# ThrowBot_RX_Main_Board.net
KiCad netlist of a schematic drawn in Altium Designer
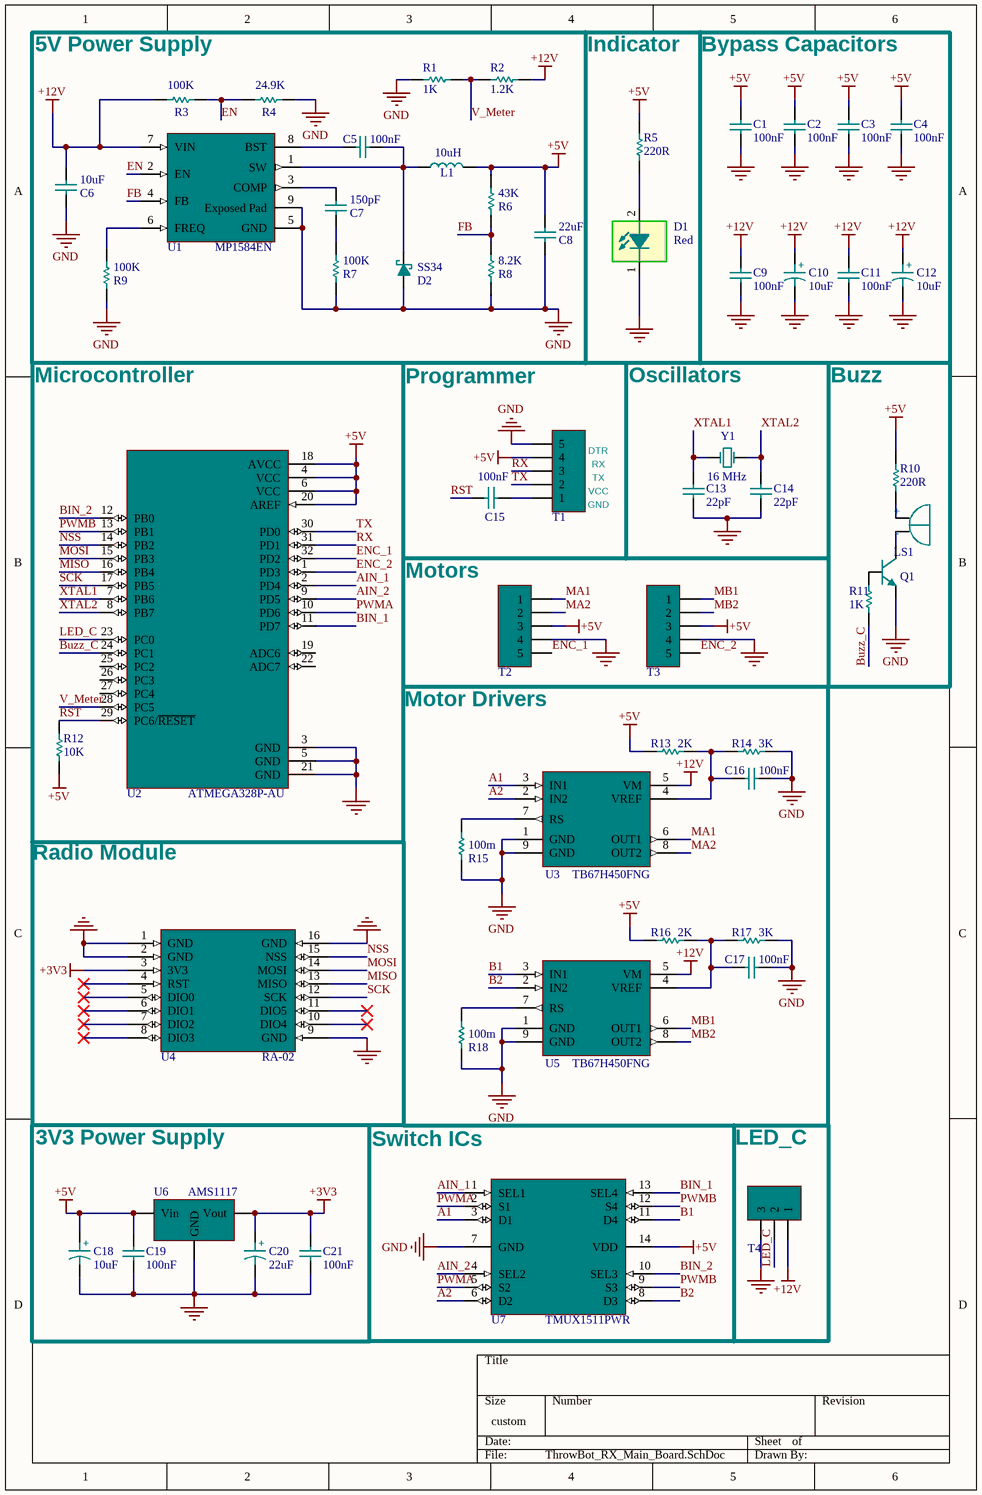
[diagram p0: ThrowBot_RX_Main_Board.SchDoc]

(export (version "E")
  (design (tool "Eeschema 10.0.6"))
  (components
    (comp (ref "C1")
      (value "Cap")
      (footprint "CAP 1206")
      (description "AVCC Cap")
      (fields (field (name "VAL-1") "100nF"))
      (libsource (lib "Throwbot") (part "Cap"))
    )
    (comp (ref "C2")
      (value "Cap")
      (footprint "CAP 1206")
      (description "VCC Cap")
      (fields (field (name "VAL-1") "100nF"))
      (libsource (lib "Throwbot") (part "Cap"))
    )
    (comp (ref "C3")
      (value "Cap")
      (footprint "CAP 1206")
      (description "VCC Cap")
      (fields (field (name "VAL-1") "100nF"))
      (libsource (lib "Throwbot") (part "Cap"))
    )
    (comp (ref "C4")
      (value "Cap")
      (footprint "CAP 1206")
      (description "AREF Cap")
      (fields (field (name "VAL-1") "100nF"))
      (libsource (lib "Throwbot") (part "Cap"))
    )
    (comp (ref "C5")
      (value "Cap")
      (footprint "CAP 1206")
      (description "1206 Capacitor")
      (fields (field (name "VAL-1") "100nF"))
      (libsource (lib "Throwbot") (part "Cap"))
    )
    (comp (ref "C6")
      (value "Cap")
      (footprint "CAP 1206")
      (description "1206 Capacitor")
      (fields (field (name "VAL-4") "10uF"))
      (libsource (lib "Throwbot") (part "Cap"))
    )
    (comp (ref "C7")
      (value "Cap")
      (footprint "CAP 1206")
      (description "1206 Capacitor")
      (fields (field (name "VAL-5") "150pF"))
      (libsource (lib "Throwbot") (part "Cap"))
    )
    (comp (ref "C8")
      (value "Cap")
      (footprint "CAP 1206")
      (description "1206 Capacitor")
      (fields (field (name "VAL-3") "22uF"))
      (libsource (lib "Throwbot") (part "Cap"))
    )
    (comp (ref "C9")
      (value "Cap")
      (footprint "CAP 1206")
      (description "Motor Power Cap")
      (fields (field (name "VAL-1") "100nF"))
      (libsource (lib "Throwbot") (part "Cap"))
    )
    (comp (ref "C10")
      (value "Cap BiPolar")
      (footprint "CAP Tantalum Size B")
      (description "Motor Power Cap")
      (fields (field (name "VAL-1") "10uF"))
      (libsource (lib "Throwbot") (part "Cap BiPolar"))
    )
    (comp (ref "C11")
      (value "Cap")
      (footprint "CAP 1206")
      (description "Motor Power Cap")
      (fields (field (name "VAL-1") "100nF"))
      (libsource (lib "Throwbot") (part "Cap"))
    )
    (comp (ref "C12")
      (value "Cap BiPolar")
      (footprint "CAP Tantalum Size B")
      (description "Motor Power Cap")
      (fields (field (name "VAL-1") "10uF"))
      (libsource (lib "Throwbot") (part "Cap BiPolar"))
    )
    (comp (ref "C13")
      (value "Cap")
      (footprint "CAP 1206")
      (description "1206 Capacitor")
      (fields (field (name "VAL-2") "22pF"))
      (libsource (lib "Throwbot") (part "Cap"))
    )
    (comp (ref "C14")
      (value "Cap")
      (footprint "CAP 1206")
      (description "1206 Capacitor")
      (fields (field (name "VAL-2") "22pF"))
      (libsource (lib "Throwbot") (part "Cap"))
    )
    (comp (ref "C15")
      (value "Cap")
      (footprint "CAP 1206")
      (description "Programmer Cap")
      (fields (field (name "VAL-1") "100nF"))
      (libsource (lib "Throwbot") (part "Cap"))
    )
    (comp (ref "C16")
      (value "Cap")
      (footprint "CAP 1206")
      (description "Motor Driver Cap")
      (fields (field (name "VAL-1") "100nF"))
      (libsource (lib "Throwbot") (part "Cap"))
    )
    (comp (ref "C17")
      (value "Cap")
      (footprint "CAP 1206")
      (description "Motor Driver Cap")
      (fields (field (name "VAL-1") "100nF"))
      (libsource (lib "Throwbot") (part "Cap"))
    )
    (comp (ref "C18")
      (value "Cap BiPolar")
      (footprint "CAP Tantalum Size B")
      (description "3.3V Regulator Cap")
      (fields (field (name "VAL-1") "10uF"))
      (libsource (lib "Throwbot") (part "Cap BiPolar"))
    )
    (comp (ref "C19")
      (value "Cap")
      (footprint "CAP 1206")
      (description "3.3V Regulator Cap")
      (fields (field (name "VAL-1") "100nF"))
      (libsource (lib "Throwbot") (part "Cap"))
    )
    (comp (ref "C20")
      (value "Cap BiPolar")
      (footprint "CAP Tantalum Size B")
      (description "3.3V Regulator Cap")
      (fields (field (name "VAL-1") "22uF"))
      (libsource (lib "Throwbot") (part "Cap BiPolar"))
    )
    (comp (ref "C21")
      (value "Cap")
      (footprint "CAP 1206")
      (description "3.3V Regulator Cap")
      (fields (field (name "VAL-1") "100nF"))
      (libsource (lib "Throwbot") (part "Cap"))
    )
    (comp (ref "D1")
      (value "LED")
      (footprint "LED 1206")
      (fields (field (name "COLOR-2") "Red"))
      (libsource (lib "Throwbot") (part "LED"))
    )
    (comp (ref "D2")
      (value "SS34")
      (footprint "SS34")
      (description "Diode Schottky 40 V 3A Surface Mount SMA")
      (fields (field (name "MF") "MDD"))
      (libsource (lib "Throwbot") (part "SS34"))
    )
    (comp (ref "L1")
      (value "10uH")
      (footprint "IND 10uH")
      (description "Inductor")
      (fields (field (name "PUBLISHER") "Altium Limited"))
      (libsource (lib "Throwbot") (part "Inductor"))
    )
    (comp (ref "LS1")
      (value "Buzzer-5V")
      (footprint "Buzzer-5V")
      (libsource (lib "Throwbot") (part "Buzzer-5V"))
    )
    (comp (ref "Q1")
      (value "BC847")
      (footprint "BC847-SOT23")
      (description "NPN General-purpose Transistor")
      (fields (field (name "DESIGNER") "Abbas Basereh"))
      (libsource (lib "Throwbot") (part "BC847"))
    )
    (comp (ref "R1")
      (value "Resistor")
      (footprint "RES 1206")
      (fields (field (name "VAL-1") "1K"))
      (libsource (lib "Throwbot") (part "Resistor"))
    )
    (comp (ref "R2")
      (value "Resistor")
      (footprint "RES 1206")
      (fields (field (name "VAL-12") "1.2K"))
      (libsource (lib "Throwbot") (part "Resistor"))
    )
    (comp (ref "R3")
      (value "Resistor")
      (footprint "RES 1206")
      (fields (field (name "VAL-4") "100K"))
      (libsource (lib "Throwbot") (part "Resistor"))
    )
    (comp (ref "R4")
      (value "Resistor")
      (footprint "RES 1206")
      (fields (field (name "VAL-5") "24.9K"))
      (libsource (lib "Throwbot") (part "Resistor"))
    )
    (comp (ref "R5")
      (value "Resistor")
      (footprint "RES 1206")
      (fields (field (name "VAL-3") "220R"))
      (libsource (lib "Throwbot") (part "Resistor"))
    )
    (comp (ref "R6")
      (value "Resistor")
      (footprint "RES 1206")
      (fields (field (name "VAL-7") "43K"))
      (libsource (lib "Throwbot") (part "Resistor"))
    )
    (comp (ref "R7")
      (value "Resistor")
      (footprint "RES 1206")
      (fields (field (name "VAL-4") "100K"))
      (libsource (lib "Throwbot") (part "Resistor"))
    )
    (comp (ref "R8")
      (value "Resistor")
      (footprint "RES 1206")
      (fields (field (name "VAL-6") "8.2K"))
      (libsource (lib "Throwbot") (part "Resistor"))
    )
    (comp (ref "R9")
      (value "Resistor")
      (footprint "RES 1206")
      (fields (field (name "VAL-4") "100K"))
      (libsource (lib "Throwbot") (part "Resistor"))
    )
    (comp (ref "R10")
      (value "Resistor")
      (footprint "RES 1206")
      (fields (field (name "VAL-3") "220R"))
      (libsource (lib "Throwbot") (part "Resistor"))
    )
    (comp (ref "R11")
      (value "Resistor")
      (footprint "RES 1206")
      (fields (field (name "VAL-1") "1K"))
      (libsource (lib "Throwbot") (part "Resistor"))
    )
    (comp (ref "R12")
      (value "Resistor")
      (footprint "RES 1206")
      (fields (field (name "VAL-2") "10K"))
      (libsource (lib "Throwbot") (part "Resistor"))
    )
    (comp (ref "R13")
      (value "Resistor")
      (footprint "RES 1206")
      (fields (field (name "VAL-11") "2K"))
      (libsource (lib "Throwbot") (part "Resistor"))
    )
    (comp (ref "R14")
      (value "Resistor")
      (footprint "RES 1206")
      (fields (field (name "VAL-10") "3K"))
      (libsource (lib "Throwbot") (part "Resistor"))
    )
    (comp (ref "R15")
      (value "Resistor")
      (footprint "RES 1206")
      (fields (field (name "VAL-9") "100m"))
      (libsource (lib "Throwbot") (part "Resistor"))
    )
    (comp (ref "R16")
      (value "Resistor")
      (footprint "RES 1206")
      (fields (field (name "VAL-11") "2K"))
      (libsource (lib "Throwbot") (part "Resistor"))
    )
    (comp (ref "R17")
      (value "Resistor")
      (footprint "RES 1206")
      (fields (field (name "VAL-10") "3K"))
      (libsource (lib "Throwbot") (part "Resistor"))
    )
    (comp (ref "R18")
      (value "Resistor")
      (footprint "RES 1206")
      (fields (field (name "VAL-9") "100m"))
      (libsource (lib "Throwbot") (part "Resistor"))
    )
    (comp (ref "T1") (value "5 Pin Socket") (footprint "XH-5AW") (libsource (lib "") (part "5 Pin Socket_1")))
    (comp (ref "T2")
      (value "5 Pin Socket")
      (footprint "XH-5AW")
      (libsource (lib "Throwbot") (part "5 Pin Socket"))
    )
    (comp (ref "T3")
      (value "5 Pin Socket")
      (footprint "XH-5AW")
      (libsource (lib "Throwbot") (part "5 Pin Socket"))
    )
    (comp (ref "T4")
      (value "3 Pin Socket")
      (footprint "XH-3AW")
      (libsource (lib "Throwbot") (part "3 Pin Socket"))
    )
    (comp (ref "U1")
      (value "MP1584EN")
      (footprint "MP1584EN")
      (fields (field (name "MF") "Monolithic Power"))
      (libsource (lib "Throwbot") (part "MP1584EN"))
    )
    (comp (ref "U2")
      (value "ATMEGA328P-AU")
      (footprint "ATmega328")
      (description "ATmega 328 Microcontroller")
      (libsource (lib "Throwbot") (part "ATMEGA328P-AU"))
    )
    (comp (ref "U3")
      (value "TB67H450FNG")
      (footprint "TB67H450FNG")
      (description "Motor Driver")
      (libsource (lib "Throwbot") (part "TB67H450FNG"))
    )
    (comp (ref "U4")
      (value "RA-02")
      (footprint "RA-02")
      (description "LoRa RA-02")
      (libsource (lib "Throwbot") (part "RA-02"))
    )
    (comp (ref "U5")
      (value "TB67H450FNG")
      (footprint "TB67H450FNG")
      (description "Motor Driver")
      (libsource (lib "Throwbot") (part "TB67H450FNG"))
    )
    (comp (ref "U6")
      (value "AMS1117")
      (footprint "AMS1117")
      (description "3V3 Regulator")
      (libsource (lib "Throwbot") (part "AMS1117"))
    )
    (comp (ref "U7")
      (value "TMUX1511PWR")
      (footprint "TMUX1511PWR")
      (libsource (lib "Throwbot") (part "TMUX1511PWR"))
    )
    (comp (ref "Y1")
      (value "XTAL")
      (footprint "Crystal-5032")
      (description "XTAL Crystal")
      (fields (field (name "VAL-2") "16 MHz"))
      (libsource (lib "Throwbot") (part "XTAL"))
    )
  )
  (nets
    (net (code "1") (name "+3V3") (class "Default")
      (node (ref "C20") (pin "1") (pinfunction "1_1") (pintype "passive"))
      (node (ref "C21") (pin "1") (pinfunction "1_1") (pintype "passive"))
      (node (ref "U4") (pin "3") (pinfunction "3V3_3") (pintype "input"))
      (node (ref "U6") (pin "2") (pinfunction "Vout_2") (pintype "power_in"))
    )
    (net (code "2") (name "+5V") (class "Default")
      (node (ref "C1") (pin "1") (pinfunction "1_1") (pintype "passive"))
      (node (ref "C18") (pin "1") (pinfunction "1_1") (pintype "passive"))
      (node (ref "C19") (pin "1") (pinfunction "1_1") (pintype "passive"))
      (node (ref "C2") (pin "1") (pinfunction "1_1") (pintype "passive"))
      (node (ref "C3") (pin "1") (pinfunction "1_1") (pintype "passive"))
      (node (ref "C4") (pin "1") (pinfunction "1_1") (pintype "passive"))
      (node (ref "C8") (pin "2") (pinfunction "2_2") (pintype "passive"))
      (node (ref "L1") (pin "2") (pinfunction "2_2") (pintype "passive"))
      (node (ref "R10") (pin "2") (pinfunction "2_2") (pintype "passive"))
      (node (ref "R12") (pin "2") (pinfunction "2_2") (pintype "passive"))
      (node (ref "R13") (pin "2") (pinfunction "2_2") (pintype "passive"))
      (node (ref "R16") (pin "2") (pinfunction "2_2") (pintype "passive"))
      (node (ref "R5") (pin "2") (pinfunction "2_2") (pintype "passive"))
      (node (ref "R6") (pin "2") (pinfunction "2_2") (pintype "passive"))
      (node (ref "T1") (pin "4") (pinfunction "4_4") (pintype "passive"))
      (node (ref "T2") (pin "3") (pinfunction "3_3") (pintype "passive"))
      (node (ref "T3") (pin "3") (pinfunction "3_3") (pintype "passive"))
      (node (ref "U2") (pin "18") (pinfunction "AVCC_18") (pintype "power_in"))
      (node (ref "U2") (pin "20") (pinfunction "AREF_20") (pintype "input"))
      (node (ref "U2") (pin "4") (pinfunction "VCC_4") (pintype "power_in"))
      (node (ref "U2") (pin "6") (pinfunction "VCC_6") (pintype "power_in"))
      (node (ref "U6") (pin "3") (pinfunction "Vin_3") (pintype "power_in"))
      (node (ref "U7") (pin "14") (pinfunction "VDD_14") (pintype "power_in"))
    )
    (net (code "3") (name "+12V") (class "Default")
      (node (ref "C10") (pin "1") (pinfunction "1_1") (pintype "passive"))
      (node (ref "C11") (pin "1") (pinfunction "1_1") (pintype "passive"))
      (node (ref "C12") (pin "1") (pinfunction "1_1") (pintype "passive"))
      (node (ref "C6") (pin "2") (pinfunction "2_2") (pintype "passive"))
      (node (ref "C9") (pin "1") (pinfunction "1_1") (pintype "passive"))
      (node (ref "R2") (pin "2") (pinfunction "2_2") (pintype "passive"))
      (node (ref "R3") (pin "2") (pinfunction "2_2") (pintype "passive"))
      (node (ref "T4") (pin "1") (pinfunction "1_1") (pintype "passive"))
      (node (ref "U1") (pin "7") (pinfunction "VIN_7") (pintype "input"))
      (node (ref "U3") (pin "5") (pinfunction "VM_5") (pintype "power_in"))
      (node (ref "U5") (pin "5") (pinfunction "VM_5") (pintype "power_in"))
    )
    (net (code "4") (name "/A1") (class "Default")
      (node (ref "U3") (pin "3") (pinfunction "IN1_3") (pintype "input"))
      (node (ref "U7") (pin "3") (pinfunction "D1_3") (pintype "bidirectional"))
    )
    (net (code "5") (name "/A2") (class "Default")
      (node (ref "U3") (pin "2") (pinfunction "IN2_2") (pintype "input"))
      (node (ref "U7") (pin "6") (pinfunction "D2_6") (pintype "bidirectional"))
    )
    (net (code "6") (name "/AIN_1") (class "Default")
      (node (ref "U2") (pin "2") (pinfunction "PD4_2") (pintype "bidirectional"))
      (node (ref "U7") (pin "1") (pinfunction "SEL1_1") (pintype "input"))
    )
    (net (code "7") (name "/AIN_2") (class "Default")
      (node (ref "U2") (pin "9") (pinfunction "PD5_9") (pintype "bidirectional"))
      (node (ref "U7") (pin "4") (pinfunction "SEL2_4") (pintype "input"))
    )
    (net (code "8") (name "/B1") (class "Default")
      (node (ref "U5") (pin "3") (pinfunction "IN1_3") (pintype "input"))
      (node (ref "U7") (pin "11") (pinfunction "D4_11") (pintype "bidirectional"))
    )
    (net (code "9") (name "/B2") (class "Default")
      (node (ref "U5") (pin "2") (pinfunction "IN2_2") (pintype "input"))
      (node (ref "U7") (pin "8") (pinfunction "D3_8") (pintype "bidirectional"))
    )
    (net (code "10") (name "/BIN_1") (class "Default")
      (node (ref "U2") (pin "11") (pinfunction "PD7_11") (pintype "bidirectional"))
      (node (ref "U7") (pin "13") (pinfunction "SEL4_13") (pintype "input"))
    )
    (net (code "11") (name "/BIN_2") (class "Default")
      (node (ref "U2") (pin "12") (pinfunction "PB0_12") (pintype "bidirectional"))
      (node (ref "U7") (pin "10") (pinfunction "SEL3_10") (pintype "input"))
    )
    (net (code "12") (name "/Buzz_C") (class "Default")
      (node (ref "R11") (pin "1") (pinfunction "1_1") (pintype "passive"))
      (node (ref "U2") (pin "24") (pinfunction "PC1_24") (pintype "bidirectional"))
    )
    (net (code "13") (name "/EN") (class "Default")
      (node (ref "R3") (pin "1") (pinfunction "1_1") (pintype "passive"))
      (node (ref "R4") (pin "1") (pinfunction "1_1") (pintype "passive"))
      (node (ref "U1") (pin "2") (pinfunction "EN_2") (pintype "input"))
    )
    (net (code "14") (name "/ENC_1") (class "Default")
      (node (ref "T2") (pin "5") (pinfunction "5_5") (pintype "passive"))
      (node (ref "U2") (pin "32") (pinfunction "PD2_32") (pintype "bidirectional"))
    )
    (net (code "15") (name "/ENC_2") (class "Default")
      (node (ref "T3") (pin "5") (pinfunction "5_5") (pintype "passive"))
      (node (ref "U2") (pin "1") (pinfunction "PD3_1") (pintype "bidirectional"))
    )
    (net (code "16") (name "/FB") (class "Default")
      (node (ref "R6") (pin "1") (pinfunction "1_1") (pintype "passive"))
      (node (ref "R8") (pin "2") (pinfunction "2_2") (pintype "passive"))
      (node (ref "U1") (pin "4") (pinfunction "FB_4") (pintype "input"))
    )
    (net (code "17") (name "/LED_C") (class "Default")
      (node (ref "T4") (pin "2") (pinfunction "2_2") (pintype "passive"))
      (node (ref "U2") (pin "23") (pinfunction "PC0_23") (pintype "bidirectional"))
    )
    (net (code "18") (name "/MA1") (class "Default")
      (node (ref "T2") (pin "1") (pinfunction "1_1") (pintype "passive"))
      (node (ref "U3") (pin "6") (pinfunction "OUT1_6") (pintype "output"))
    )
    (net (code "19") (name "/MA2") (class "Default")
      (node (ref "T2") (pin "2") (pinfunction "2_2") (pintype "passive"))
      (node (ref "U3") (pin "8") (pinfunction "OUT2_8") (pintype "output"))
    )
    (net (code "20") (name "/MB1") (class "Default")
      (node (ref "T3") (pin "1") (pinfunction "1_1") (pintype "passive"))
      (node (ref "U5") (pin "6") (pinfunction "OUT1_6") (pintype "output"))
    )
    (net (code "21") (name "/MB2") (class "Default")
      (node (ref "T3") (pin "2") (pinfunction "2_2") (pintype "passive"))
      (node (ref "U5") (pin "8") (pinfunction "OUT2_8") (pintype "output"))
    )
    (net (code "22") (name "/MISO") (class "Default")
      (node (ref "U2") (pin "16") (pinfunction "PB4_16") (pintype "bidirectional"))
      (node (ref "U4") (pin "13") (pinfunction "MISO_13") (pintype "bidirectional"))
    )
    (net (code "23") (name "/MOSI") (class "Default")
      (node (ref "U2") (pin "15") (pinfunction "PB3_15") (pintype "bidirectional"))
      (node (ref "U4") (pin "14") (pinfunction "MOSI_14") (pintype "bidirectional"))
    )
    (net (code "24") (name "/NSS") (class "Default")
      (node (ref "U2") (pin "14") (pinfunction "PB2_14") (pintype "bidirectional"))
      (node (ref "U4") (pin "15") (pinfunction "NSS_15") (pintype "bidirectional"))
    )
    (net (code "25") (name "/PWMA") (class "Default")
      (node (ref "U2") (pin "10") (pinfunction "PD6_10") (pintype "bidirectional"))
      (node (ref "U7") (pin "2") (pinfunction "S1_2") (pintype "bidirectional"))
      (node (ref "U7") (pin "5") (pinfunction "S2_5") (pintype "bidirectional"))
    )
    (net (code "26") (name "/PWMB") (class "Default")
      (node (ref "U2") (pin "13") (pinfunction "PB1_13") (pintype "bidirectional"))
      (node (ref "U7") (pin "12") (pinfunction "S4_12") (pintype "bidirectional"))
      (node (ref "U7") (pin "9") (pinfunction "S3_9") (pintype "bidirectional"))
    )
    (net (code "27") (name "/RST") (class "Default")
      (node (ref "C15") (pin "1") (pinfunction "1_1") (pintype "passive"))
      (node (ref "R12") (pin "1") (pinfunction "1_1") (pintype "passive"))
      (node (ref "U2") (pin "29") (pinfunction "PC6/~{RESET}_29") (pintype "bidirectional"))
    )
    (net (code "28") (name "/RX") (class "Default")
      (node (ref "T1") (pin "3") (pinfunction "3_3") (pintype "passive"))
      (node (ref "U2") (pin "31") (pinfunction "PD1_31") (pintype "bidirectional"))
    )
    (net (code "29") (name "/SCK") (class "Default")
      (node (ref "U2") (pin "17") (pinfunction "PB5_17") (pintype "bidirectional"))
      (node (ref "U4") (pin "12") (pinfunction "SCK_12") (pintype "bidirectional"))
    )
    (net (code "30") (name "/TX") (class "Default")
      (node (ref "T1") (pin "2") (pinfunction "2_2") (pintype "passive"))
      (node (ref "U2") (pin "30") (pinfunction "PD0_30") (pintype "bidirectional"))
    )
    (net (code "31") (name "/V_Meter") (class "Default")
      (node (ref "R1") (pin "2") (pinfunction "2_2") (pintype "passive"))
      (node (ref "R2") (pin "1") (pinfunction "1_1") (pintype "passive"))
      (node (ref "U2") (pin "28") (pinfunction "PC5_28") (pintype "bidirectional"))
    )
    (net (code "32") (name "/XTAL1") (class "Default")
      (node (ref "C13") (pin "2") (pinfunction "2_2") (pintype "passive"))
      (node (ref "U2") (pin "7") (pinfunction "PB6_7") (pintype "bidirectional"))
      (node (ref "Y1") (pin "1") (pinfunction "OSC1_1") (pintype "passive"))
    )
    (net (code "33") (name "/XTAL2") (class "Default")
      (node (ref "C14") (pin "2") (pinfunction "2_2") (pintype "passive"))
      (node (ref "U2") (pin "8") (pinfunction "PB7_8") (pintype "bidirectional"))
      (node (ref "Y1") (pin "2") (pinfunction "OSC2_2") (pintype "passive"))
    )
    (net (code "34") (name "GND") (class "Default")
      (node (ref "C1") (pin "2") (pinfunction "2_2") (pintype "passive"))
      (node (ref "C10") (pin "2") (pinfunction "2_2") (pintype "passive"))
      (node (ref "C11") (pin "2") (pinfunction "2_2") (pintype "passive"))
      (node (ref "C12") (pin "2") (pinfunction "2_2") (pintype "passive"))
      (node (ref "C13") (pin "1") (pinfunction "1_1") (pintype "passive"))
      (node (ref "C14") (pin "1") (pinfunction "1_1") (pintype "passive"))
      (node (ref "C16") (pin "2") (pinfunction "2_2") (pintype "passive"))
      (node (ref "C17") (pin "2") (pinfunction "2_2") (pintype "passive"))
      (node (ref "C18") (pin "2") (pinfunction "2_2") (pintype "passive"))
      (node (ref "C19") (pin "2") (pinfunction "2_2") (pintype "passive"))
      (node (ref "C2") (pin "2") (pinfunction "2_2") (pintype "passive"))
      (node (ref "C20") (pin "2") (pinfunction "2_2") (pintype "passive"))
      (node (ref "C21") (pin "2") (pinfunction "2_2") (pintype "passive"))
      (node (ref "C3") (pin "2") (pinfunction "2_2") (pintype "passive"))
      (node (ref "C4") (pin "2") (pinfunction "2_2") (pintype "passive"))
      (node (ref "C6") (pin "1") (pinfunction "1_1") (pintype "passive"))
      (node (ref "C8") (pin "1") (pinfunction "1_1") (pintype "passive"))
      (node (ref "C9") (pin "2") (pinfunction "2_2") (pintype "passive"))
      (node (ref "D1") (pin "1") (pinfunction "1_1") (pintype "passive"))
      (node (ref "D2") (pin "1") (pinfunction "A_1") (pintype "passive"))
      (node (ref "Q1") (pin "2") (pinfunction "E_2") (pintype "passive"))
      (node (ref "R1") (pin "1") (pinfunction "1_1") (pintype "passive"))
      (node (ref "R14") (pin "1") (pinfunction "1_1") (pintype "passive"))
      (node (ref "R15") (pin "1") (pinfunction "1_1") (pintype "passive"))
      (node (ref "R17") (pin "1") (pinfunction "1_1") (pintype "passive"))
      (node (ref "R18") (pin "1") (pinfunction "1_1") (pintype "passive"))
      (node (ref "R4") (pin "2") (pinfunction "2_2") (pintype "passive"))
      (node (ref "R7") (pin "1") (pinfunction "1_1") (pintype "passive"))
      (node (ref "R8") (pin "1") (pinfunction "1_1") (pintype "passive"))
      (node (ref "R9") (pin "1") (pinfunction "1_1") (pintype "passive"))
      (node (ref "T1") (pin "5") (pinfunction "5_5") (pintype "passive"))
      (node (ref "T2") (pin "4") (pinfunction "4_4") (pintype "passive"))
      (node (ref "T3") (pin "4") (pinfunction "4_4") (pintype "passive"))
      (node (ref "T4") (pin "3") (pinfunction "3_3") (pintype "passive"))
      (node (ref "U1") (pin "5") (pinfunction "GND_5") (pintype "power_in"))
      (node (ref "U1") (pin "9") (pinfunction "Exposed_Pad_9") (pintype "power_in"))
      (node (ref "U2") (pin "21") (pinfunction "GND_21") (pintype "power_in"))
      (node (ref "U2") (pin "3") (pinfunction "GND_3") (pintype "power_in"))
      (node (ref "U2") (pin "5") (pinfunction "GND_5") (pintype "power_in"))
      (node (ref "U3") (pin "1") (pinfunction "GND_1") (pintype "power_in"))
      (node (ref "U3") (pin "9") (pinfunction "GND_9") (pintype "power_in"))
      (node (ref "U4") (pin "1") (pinfunction "GND_1") (pintype "input"))
      (node (ref "U4") (pin "16") (pinfunction "GND_16") (pintype "input"))
      (node (ref "U4") (pin "2") (pinfunction "GND_2") (pintype "input"))
      (node (ref "U4") (pin "9") (pinfunction "GND_9") (pintype "input"))
      (node (ref "U5") (pin "1") (pinfunction "GND_1") (pintype "power_in"))
      (node (ref "U5") (pin "9") (pinfunction "GND_9") (pintype "power_in"))
      (node (ref "U6") (pin "1") (pinfunction "GND_1") (pintype "power_in"))
      (node (ref "U7") (pin "7") (pinfunction "GND_7") (pintype "power_in"))
    )
    (net (code "35") (name "Net-(C7-Pad1)") (class "Default")
      (node (ref "C7") (pin "1") (pinfunction "1_1") (pintype "passive"))
      (node (ref "R7") (pin "2") (pinfunction "2_2") (pintype "passive"))
    )
    (net (code "36") (name "Net-(C15-Pad2)") (class "Default")
      (node (ref "C15") (pin "2") (pinfunction "2_2") (pintype "passive"))
      (node (ref "T1") (pin "1") (pinfunction "1_1") (pintype "passive"))
    )
    (net (code "37") (name "Net-(D1-Pad2)") (class "Default")
      (node (ref "D1") (pin "2") (pinfunction "2_2") (pintype "passive"))
      (node (ref "R5") (pin "1") (pinfunction "1_1") (pintype "passive"))
    )
    (net (code "38") (name "Net-(D2-K)") (class "Default")
      (node (ref "C5") (pin "1") (pinfunction "1_1") (pintype "passive"))
      (node (ref "D2") (pin "2") (pinfunction "K_2") (pintype "passive"))
      (node (ref "L1") (pin "1") (pinfunction "1_1") (pintype "passive"))
      (node (ref "U1") (pin "1") (pinfunction "SW_1") (pintype "output"))
    )
    (net (code "39") (name "Net-(LS1-NEG)") (class "Default")
      (node (ref "LS1") (pin "N") (pinfunction "NEG_N") (pintype "passive"))
      (node (ref "Q1") (pin "3") (pinfunction "C_3") (pintype "passive"))
    )
    (net (code "40") (name "Net-(LS1-POS)") (class "Default")
      (node (ref "LS1") (pin "P") (pinfunction "POS_P") (pintype "passive"))
      (node (ref "R10") (pin "1") (pinfunction "1_1") (pintype "passive"))
    )
    (net (code "41") (name "Net-(Q1-B)") (class "Default")
      (node (ref "Q1") (pin "1") (pinfunction "B_1") (pintype "passive"))
      (node (ref "R11") (pin "2") (pinfunction "2_2") (pintype "passive"))
    )
    (net (code "42") (name "Net-(U1-BST)") (class "Default")
      (node (ref "C5") (pin "2") (pinfunction "2_2") (pintype "passive"))
      (node (ref "U1") (pin "8") (pinfunction "BST_8") (pintype "passive"))
    )
    (net (code "43") (name "Net-(U1-COMP)") (class "Default")
      (node (ref "C7") (pin "2") (pinfunction "2_2") (pintype "passive"))
      (node (ref "U1") (pin "3") (pinfunction "COMP_3") (pintype "output"))
    )
    (net (code "44") (name "Net-(U1-FREQ)") (class "Default")
      (node (ref "R9") (pin "2") (pinfunction "2_2") (pintype "passive"))
      (node (ref "U1") (pin "6") (pinfunction "FREQ_6") (pintype "input"))
    )
    (net (code "45") (name "Net-(U3-RS)") (class "Default")
      (node (ref "R15") (pin "2") (pinfunction "2_2") (pintype "passive"))
      (node (ref "U3") (pin "7") (pinfunction "RS_7") (pintype "output"))
    )
    (net (code "46") (name "Net-(U3-VREF)") (class "Default")
      (node (ref "C16") (pin "1") (pinfunction "1_1") (pintype "passive"))
      (node (ref "R13") (pin "1") (pinfunction "1_1") (pintype "passive"))
      (node (ref "R14") (pin "2") (pinfunction "2_2") (pintype "passive"))
      (node (ref "U3") (pin "4") (pinfunction "VREF_4") (pintype "power_in"))
    )
    (net (code "47") (name "Net-(U5-RS)") (class "Default")
      (node (ref "R18") (pin "2") (pinfunction "2_2") (pintype "passive"))
      (node (ref "U5") (pin "7") (pinfunction "RS_7") (pintype "output"))
    )
    (net (code "48") (name "Net-(U5-VREF)") (class "Default")
      (node (ref "C17") (pin "1") (pinfunction "1_1") (pintype "passive"))
      (node (ref "R16") (pin "1") (pinfunction "1_1") (pintype "passive"))
      (node (ref "R17") (pin "2") (pinfunction "2_2") (pintype "passive"))
      (node (ref "U5") (pin "4") (pinfunction "VREF_4") (pintype "power_in"))
    )
    (net (code "49") (name "unconnected-(U2-ADC6-Pad19)") (class "Default")
      (node (ref "U2") (pin "19") (pinfunction "ADC6_19") (pintype "bidirectional"))
    )
    (net (code "50") (name "unconnected-(U2-ADC7-Pad22)") (class "Default")
      (node (ref "U2") (pin "22") (pinfunction "ADC7_22") (pintype "bidirectional"))
    )
    (net (code "51") (name "unconnected-(U2-PC2-Pad25)") (class "Default")
      (node (ref "U2") (pin "25") (pinfunction "PC2_25") (pintype "bidirectional"))
    )
    (net (code "52") (name "unconnected-(U2-PC3-Pad26)") (class "Default")
      (node (ref "U2") (pin "26") (pinfunction "PC3_26") (pintype "bidirectional"))
    )
    (net (code "53") (name "unconnected-(U2-PC4-Pad27)") (class "Default")
      (node (ref "U2") (pin "27") (pinfunction "PC4_27") (pintype "bidirectional"))
    )
    (net (code "54") (name "unconnected-(U4-DIO0-Pad5)") (class "Default")
      (node (ref "U4") (pin "5") (pinfunction "DIO0_5") (pintype "bidirectional+no_connect"))
    )
    (net (code "55") (name "unconnected-(U4-DIO1-Pad6)") (class "Default")
      (node (ref "U4") (pin "6") (pinfunction "DIO1_6") (pintype "bidirectional+no_connect"))
    )
    (net (code "56") (name "unconnected-(U4-DIO2-Pad7)") (class "Default")
      (node (ref "U4") (pin "7") (pinfunction "DIO2_7") (pintype "bidirectional+no_connect"))
    )
    (net (code "57") (name "unconnected-(U4-DIO3-Pad8)") (class "Default")
      (node (ref "U4") (pin "8") (pinfunction "DIO3_8") (pintype "bidirectional+no_connect"))
    )
    (net (code "58") (name "unconnected-(U4-DIO4-Pad10)") (class "Default")
      (node (ref "U4") (pin "10") (pinfunction "DIO4_10") (pintype "bidirectional+no_connect"))
    )
    (net (code "59") (name "unconnected-(U4-DIO5-Pad11)") (class "Default")
      (node (ref "U4") (pin "11") (pinfunction "DIO5_11") (pintype "bidirectional+no_connect"))
    )
    (net (code "60") (name "unconnected-(U4-RST-Pad4)") (class "Default")
      (node (ref "U4") (pin "4") (pinfunction "RST_4") (pintype "input+no_connect"))
    )
  )
)
